# IMU_Board_IMU_CG.net
KiCad netlist of a schematic drawn in Altium Designer
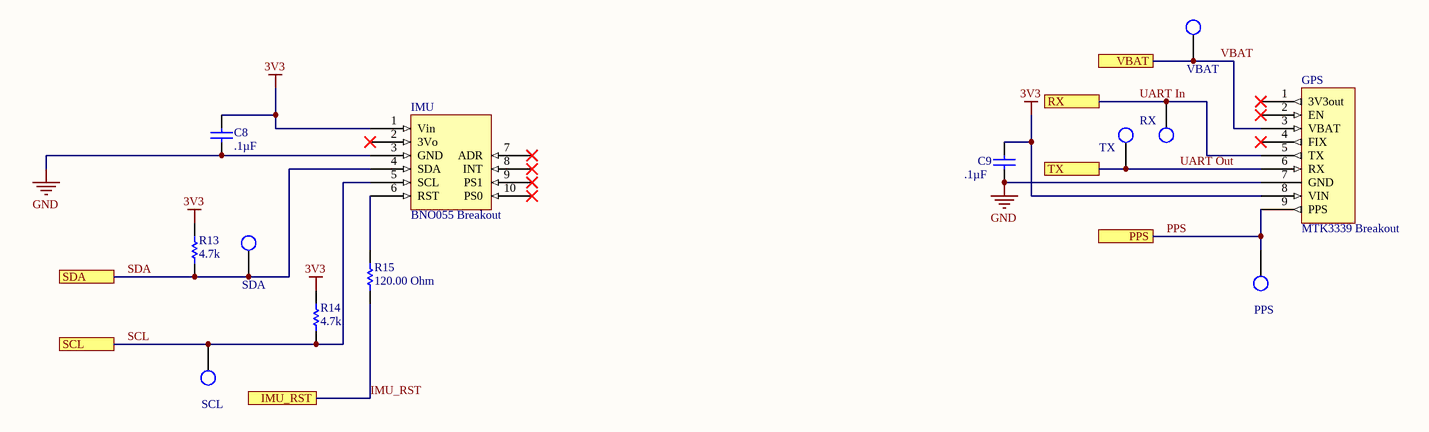
[diagram p0: IMU_Board_IMU_CG.SchDoc]

(export (version "E")
  (design (tool "Eeschema 10.0.6"))
  (components
    (comp (ref "C8")
      (value "Capacitor 0805")
      (footprint "Cap 0805")
      (description "Standard Capacitor")
      (fields (field (name "MANUFACTURER") "AVX") (field (name "CAPACITANCE") ".1µF"))
      (libsource (lib "Standard Cap") (part "Capacitor 0805"))
    )
    (comp (ref "C9")
      (value "Capacitor 0805")
      (footprint "Cap 0805")
      (description "Standard Capacitor")
      (fields (field (name "MANUFACTURER") "AVX") (field (name "CAPACITANCE") ".1µF"))
      (libsource (lib "Standard Cap") (part "Capacitor 0805"))
    )
    (comp (ref "GPS")
      (value "MTK3339 Breakout")
      (footprint "MTK3339 Breakout")
      (libsource (lib "IMU IC Breakouts 2020") (part "MTK3339 Breakout"))
    )
    (comp (ref "IMU")
      (value "BNO055 Breakout")
      (footprint "BNO055 Breakout")
      (libsource (lib "IMU IC Breakouts 2020") (part "BNO055 Breakout"))
    )
    (comp (ref "PPS")
      (value "Test Point")
      (footprint "Test Point Through-hole")
      (libsource (lib "Husky Robotics Standard Library 2019-2020") (part "Test Point"))
    )
    (comp (ref "R13")
      (value "4.7k")
      (footprint "RESC0805(2012)_N")
      (description "Generic 0805 Resistor")
      (fields (field (name "TOLERANCE") "5 %") (field (name "POWER") "0.125 W"))
      (libsource (lib "CAN Termination Resistor 0805") (part "Resistor 0805"))
    )
    (comp (ref "R14")
      (value "4.7k")
      (footprint "RESC0805(2012)_N")
      (description "Generic 0805 Resistor")
      (fields (field (name "TOLERANCE") "5 %") (field (name "POWER") "0.125 W"))
      (libsource (lib "CAN Termination Resistor 0805") (part "Resistor 0805"))
    )
    (comp (ref "R15")
      (value "120.00 Ohm")
      (footprint "RESC0805(2012)_N")
      (description "Generic 0805 Resistor")
      (fields (field (name "TOLERANCE") "5 %") (field (name "POWER") "0.125 W"))
      (libsource (lib "CAN Termination Resistor 0805") (part "Resistor 0805"))
    )
    (comp (ref "RX")
      (value "Test Point")
      (footprint "Test Point Through-hole")
      (libsource (lib "Husky Robotics Standard Library 2019-2020") (part "Test Point"))
    )
    (comp (ref "SCL")
      (value "Test Point")
      (footprint "Test Point Through-hole")
      (libsource (lib "Husky Robotics Standard Library 2019-2020") (part "Test Point"))
    )
    (comp (ref "SDA")
      (value "Test Point")
      (footprint "Test Point Through-hole")
      (libsource (lib "Husky Robotics Standard Library 2019-2020") (part "Test Point"))
    )
    (comp (ref "TX")
      (value "Test Point")
      (footprint "Test Point Through-hole")
      (libsource (lib "Husky Robotics Standard Library 2019-2020") (part "Test Point"))
    )
    (comp (ref "VBAT")
      (value "Test Point")
      (footprint "Test Point Through-hole")
      (libsource (lib "Husky Robotics Standard Library 2019-2020") (part "Test Point"))
    )
  )
  (nets
    (net (code "1") (name "/IMU_RST") (class "Default")
      (node (ref "R15") (pin "1") (pinfunction "1_1") (pintype "passive"))
    )
    (net (code "2") (name "/PPS") (class "Default")
      (node (ref "GPS") (pin "9") (pinfunction "PPS_9") (pintype "output"))
      (node (ref "PPS") (pin "1") (pinfunction "1_1") (pintype "passive"))
    )
    (net (code "3") (name "/SCL") (class "Default")
      (node (ref "IMU") (pin "5") (pinfunction "SCL_5") (pintype "input"))
      (node (ref "R14") (pin "1") (pinfunction "1_1") (pintype "passive"))
      (node (ref "SCL") (pin "1") (pinfunction "1_1") (pintype "passive"))
    )
    (net (code "4") (name "/SDA") (class "Default")
      (node (ref "IMU") (pin "4") (pinfunction "SDA_4") (pintype "input"))
      (node (ref "R13") (pin "1") (pinfunction "1_1") (pintype "passive"))
      (node (ref "SDA") (pin "1") (pinfunction "1_1") (pintype "passive"))
    )
    (net (code "5") (name "/UART In") (class "Default")
      (node (ref "GPS") (pin "5") (pinfunction "TX_5") (pintype "output"))
      (node (ref "RX") (pin "1") (pinfunction "1_1") (pintype "passive"))
    )
    (net (code "6") (name "/UART Out") (class "Default")
      (node (ref "GPS") (pin "6") (pinfunction "RX_6") (pintype "input"))
      (node (ref "TX") (pin "1") (pinfunction "1_1") (pintype "passive"))
    )
    (net (code "7") (name "/VBAT") (class "Default")
      (node (ref "GPS") (pin "3") (pinfunction "VBAT_3") (pintype "input"))
      (node (ref "VBAT") (pin "1") (pinfunction "1_1") (pintype "passive"))
    )
    (net (code "8") (name "3V3") (class "Default")
      (node (ref "C8") (pin "2") (pinfunction "2_2") (pintype "passive"))
      (node (ref "C9") (pin "2") (pinfunction "2_2") (pintype "passive"))
      (node (ref "GPS") (pin "8") (pinfunction "VIN_8") (pintype "input"))
      (node (ref "IMU") (pin "1") (pinfunction "Vin_1") (pintype "input"))
      (node (ref "R13") (pin "2") (pinfunction "2_2") (pintype "passive"))
      (node (ref "R14") (pin "2") (pinfunction "2_2") (pintype "passive"))
    )
    (net (code "9") (name "GND") (class "Default")
      (node (ref "C8") (pin "1") (pinfunction "1_1") (pintype "passive"))
      (node (ref "C9") (pin "1") (pinfunction "1_1") (pintype "passive"))
      (node (ref "GPS") (pin "7") (pinfunction "GND_7") (pintype "power_in"))
      (node (ref "IMU") (pin "3") (pinfunction "GND_3") (pintype "input"))
    )
    (net (code "10") (name "Net-(IMU-RST)") (class "Default")
      (node (ref "IMU") (pin "6") (pinfunction "RST_6") (pintype "input"))
      (node (ref "R15") (pin "2") (pinfunction "2_2") (pintype "passive"))
    )
    (net (code "11") (name "unconnected-(GPS-3V3out-Pad1)") (class "Default")
      (node (ref "GPS") (pin "1") (pinfunction "3V3out_1") (pintype "output+no_connect"))
    )
    (net (code "12") (name "unconnected-(GPS-EN-Pad2)") (class "Default")
      (node (ref "GPS") (pin "2") (pinfunction "EN_2") (pintype "input+no_connect"))
    )
    (net (code "13") (name "unconnected-(GPS-FIX-Pad4)") (class "Default")
      (node (ref "GPS") (pin "4") (pinfunction "FIX_4") (pintype "output+no_connect"))
    )
    (net (code "14") (name "unconnected-(IMU-3Vo-Pad2)") (class "Default")
      (node (ref "IMU") (pin "2") (pinfunction "3Vo_2") (pintype "input+no_connect"))
    )
    (net (code "15") (name "unconnected-(IMU-ADR-Pad7)") (class "Default")
      (node (ref "IMU") (pin "7") (pinfunction "ADR_7") (pintype "input+no_connect"))
    )
    (net (code "16") (name "unconnected-(IMU-INT-Pad8)") (class "Default")
      (node (ref "IMU") (pin "8") (pinfunction "INT_8") (pintype "input+no_connect"))
    )
    (net (code "17") (name "unconnected-(IMU-PS0-Pad10)") (class "Default")
      (node (ref "IMU") (pin "10") (pinfunction "PS0_10") (pintype "input+no_connect"))
    )
    (net (code "18") (name "unconnected-(IMU-PS1-Pad9)") (class "Default")
      (node (ref "IMU") (pin "9") (pinfunction "PS1_9") (pintype "input+no_connect"))
    )
  )
)
